# ADSB_AMP_V2.net
KiCad netlist of a schematic drawn in EAGLE
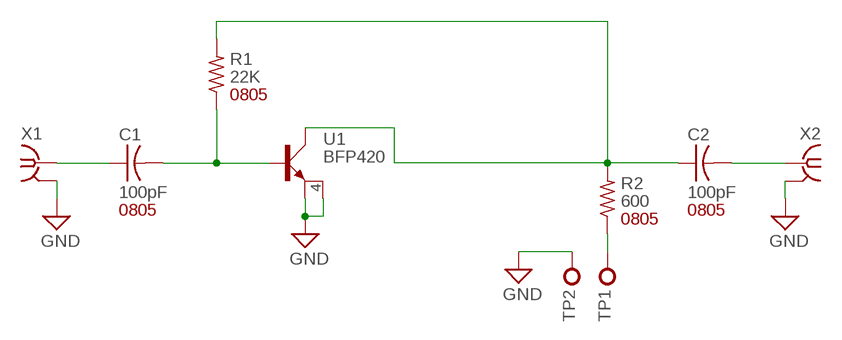
[diagram p0: schematic, sheet 1]

(export (version "E")
  (design (tool "Eeschema 10.0.6"))
  (components
    (comp (ref "C1")
      (value "100pF")
      (footprint "eagle-import:0805")
      (libsource (lib "eagle-import") (part "CAP0805"))
    )
    (comp (ref "C2")
      (value "100pF")
      (footprint "eagle-import:0805")
      (libsource (lib "eagle-import") (part "CAP0805"))
    )
    (comp (ref "R1")
      (value "22K")
      (footprint "eagle-import:0805")
      (libsource (lib "eagle-import") (part "RES0805"))
    )
    (comp (ref "R2")
      (value "600")
      (footprint "eagle-import:0805")
      (libsource (lib "eagle-import") (part "RES0805"))
    )
    (comp (ref "TP1")
      (value "TEST_POINTS76_150")
      (footprint "eagle-import:SMD_76_150")
      (libsource (lib "eagle-import") (part "TEST_POINTS76_150"))
    )
    (comp (ref "TP2")
      (value "TEST_POINTS76_150")
      (footprint "eagle-import:SMD_76_150")
      (libsource (lib "eagle-import") (part "TEST_POINTS76_150"))
    )
    (comp (ref "U1")
      (value "BFP420")
      (footprint "eagle-import:SOT343_INFINEON")
      (libsource (lib "eagle-import") (part "BFP420"))
    )
    (comp (ref "X1")
      (value "SMA-142-0701-801/806")
      (footprint "eagle-import:J502-ND-142-0701-801_806")
      (fields (field (name "MF") "JOHNSON COMPONENTS") (field (name "MPN") "142-0701-801"))
      (libsource (lib "eagle-import") (part "SMA-142-0701-801/806"))
    )
    (comp (ref "X2")
      (value "SMA-142-0701-801/806")
      (footprint "eagle-import:J502-ND-142-0701-801_806")
      (fields (field (name "MF") "JOHNSON COMPONENTS") (field (name "MPN") "142-0701-801"))
      (libsource (lib "eagle-import") (part "SMA-142-0701-801/806"))
    )
  )
  (nets
    (net (code "1") (name "GND") (class "Default")
      (node (ref "TP2") (pin "1") (pinfunction "MP_1") (pintype "passive"))
      (node (ref "U1") (pin "2") (pinfunction "E1_2") (pintype "passive"))
      (node (ref "U1") (pin "4") (pinfunction "E2_4") (pintype "passive"))
      (node (ref "X1") (pin "G@1") (pinfunction "GND_G@1") (pintype "power_in"))
      (node (ref "X2") (pin "G@1") (pinfunction "GND_G@1") (pintype "power_in"))
    )
    (net (code "2") (name "Net-(C1-Pad1)") (class "Default")
      (node (ref "C1") (pin "1") (pinfunction "1_1") (pintype "passive"))
      (node (ref "X1") (pin "1") (pinfunction "1_1") (pintype "passive"))
    )
    (net (code "3") (name "Net-(C2-Pad2)") (class "Default")
      (node (ref "C2") (pin "2") (pinfunction "2_2") (pintype "passive"))
      (node (ref "X2") (pin "1") (pinfunction "1_1") (pintype "passive"))
    )
    (net (code "4") (name "Net-(TP1-MP)") (class "Default")
      (node (ref "R2") (pin "1") (pinfunction "1_1") (pintype "passive"))
      (node (ref "TP1") (pin "1") (pinfunction "MP_1") (pintype "passive"))
    )
    (net (code "5") (name "Net-(U1-B)") (class "Default")
      (node (ref "C1") (pin "2") (pinfunction "2_2") (pintype "passive"))
      (node (ref "R1") (pin "1") (pinfunction "1_1") (pintype "passive"))
      (node (ref "U1") (pin "1") (pinfunction "B_1") (pintype "passive"))
    )
    (net (code "6") (name "Net-(U1-C)") (class "Default")
      (node (ref "C2") (pin "1") (pinfunction "1_1") (pintype "passive"))
      (node (ref "R1") (pin "2") (pinfunction "2_2") (pintype "passive"))
      (node (ref "R2") (pin "2") (pinfunction "2_2") (pintype "passive"))
      (node (ref "U1") (pin "3") (pinfunction "C_3") (pintype "passive"))
    )
  )
)
